# window-watchdog.net
KiCad netlist of a schematic drawn in Altium Designer
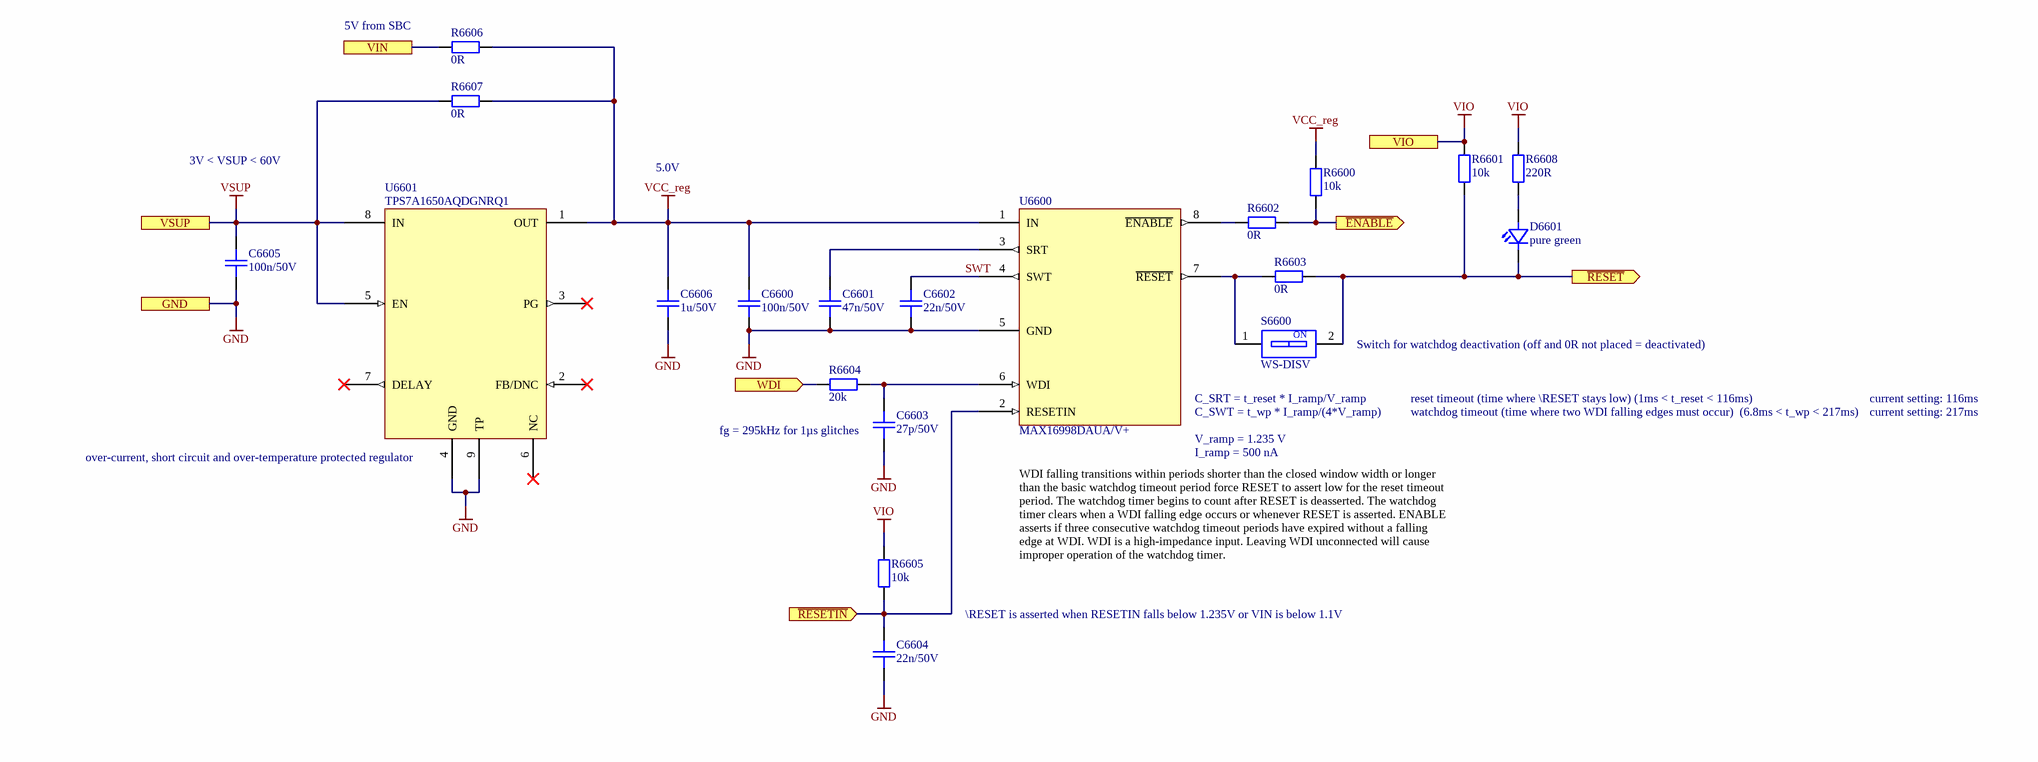
[diagram p0: window-watchdog.SchDoc]

(export (version "E")
  (design (tool "Eeschema 10.0.6"))
  (components
    (comp (ref "C6600")
      (value "100n/50V")
      (footprint "CAPC1005X06N")
      (description "MLCC")
      (fields (field (name "PART NUMBER") "gen_C_ceramic_100n_50V_X7R_0402"))
      (libsource (lib "OE750") (part "C"))
    )
    (comp (ref "C6601")
      (value "47n/50V")
      (footprint "CAPC1005X06N")
      (description "MLCC")
      (fields (field (name "PART NUMBER") "gen_C_ceramic_47n_50V_X7R_0402"))
      (libsource (lib "OE750") (part "C"))
    )
    (comp (ref "C6602")
      (value "22n/50V")
      (footprint "CAPC1005X06N")
      (description "MLCC")
      (fields (field (name "PART NUMBER") "gen_C_ceramic_22n_50V_X7R_0402"))
      (libsource (lib "OE750") (part "C"))
    )
    (comp (ref "C6603")
      (value "27p/50V")
      (footprint "CAPC1608X08N")
      (description "MLCC")
      (fields (field (name "PART NUMBER") "gen_C_ceramic_27p_50V_NP0_0603"))
      (libsource (lib "OE750") (part "C"))
    )
    (comp (ref "C6604")
      (value "22n/50V")
      (footprint "CAPC1005X06N")
      (description "MLCC")
      (fields (field (name "PART NUMBER") "gen_C_ceramic_22n_50V_X7R_0402"))
      (libsource (lib "OE750") (part "C"))
    )
    (comp (ref "C6605")
      (value "100n/50V")
      (footprint "CAPC1005X06N")
      (description "MLCC")
      (fields (field (name "PART NUMBER") "gen_C_ceramic_100n_50V_X7R_0402"))
      (libsource (lib "OE750") (part "C"))
    )
    (comp (ref "C6606")
      (value "1u/50V")
      (footprint "CAPC1608X08N")
      (description "MLCC")
      (fields (field (name "PART NUMBER") "gen_C_ceramic_1u_50V_X7R_0603") (field (name "TOLERANCE") "± 10%"))
      (libsource (lib "OE750") (part "C"))
    )
    (comp (ref "D6601")
      (value "pure green")
      (footprint "LEDC1608X07N")
      (description "TLMP1100-GS08")
      (fields (field (name "PART NUMBER") "LED_0603_pure_green_AECQ") (field (name "MANUFACTURER") "Vishay"))
      (libsource (lib "OE750") (part "D_LED"))
    )
    (comp (ref "R6600")
      (value "10k")
      (footprint "RESC1005X04N")
      (description "SMD Resistor 10k 0402")
      (fields (field (name "PART NUMBER") "gen_R_10k_0402") (field (name "TOLERANCE") "1%"))
      (libsource (lib "OE750") (part "R"))
    )
    (comp (ref "R6601")
      (value "10k")
      (footprint "RESC1005X04N")
      (description "SMD Resistor 10k 0402")
      (fields (field (name "PART NUMBER") "gen_R_10k_0402") (field (name "TOLERANCE") "1%"))
      (libsource (lib "OE750") (part "R"))
    )
    (comp (ref "R6602")
      (value "0R")
      (footprint "RESC1005X04N")
      (description "SMD Resistor 0R 0402")
      (fields (field (name "PART NUMBER") "gen_R_0R_0402") (field (name "POWER") "0.063W"))
      (libsource (lib "OE750") (part "R"))
    )
    (comp (ref "R6603")
      (value "0R")
      (footprint "RESC1005X04N")
      (description "SMD Resistor 0R 0402")
      (fields (field (name "PART NUMBER") "gen_R_0R_0402") (field (name "POWER") "0.063W"))
      (libsource (lib "OE750") (part "R"))
    )
    (comp (ref "R6604")
      (value "20k")
      (footprint "RESC1005X04N")
      (description "SMD Resistor 20k 0402")
      (fields (field (name "PART NUMBER") "gen_R_20k_0402") (field (name "TOLERANCE") "1%"))
      (libsource (lib "OE750") (part "R"))
    )
    (comp (ref "R6605")
      (value "10k")
      (footprint "RESC1005X04N")
      (description "SMD Resistor 10k 0402")
      (fields (field (name "PART NUMBER") "gen_R_10k_0402") (field (name "TOLERANCE") "1%"))
      (libsource (lib "OE750") (part "R"))
    )
    (comp (ref "R6606")
      (value "0R")
      (footprint "RESC1005X04N")
      (description "SMD Resistor 0R 0402")
      (fields (field (name "PART NUMBER") "gen_R_0R_0402") (field (name "POWER") "0.063W"))
      (libsource (lib "OE750") (part "R"))
    )
    (comp (ref "R6607")
      (value "0R")
      (footprint "RESC1005X04N")
      (description "SMD Resistor 0R 0402")
      (fields (field (name "PART NUMBER") "gen_R_0R_0402") (field (name "POWER") "0.063W"))
      (libsource (lib "OE750") (part "R"))
    )
    (comp (ref "R6608")
      (value "220R")
      (footprint "RESC1005X04N")
      (description "SMD Resistor 220R 0402")
      (fields (field (name "PART NUMBER") "gen_R_220R_0402") (field (name "TOLERANCE") "1%"))
      (libsource (lib "OE750") (part "R"))
    )
    (comp (ref "S6600")
      (value "WS-DISV")
      (footprint "WE_416131160801")
      (description "WS-DISV Small Compact SMT DipSwitch")
      (fields (field (name "PART NUMBER") "WE_416131160801") (field (name "MANUFACTURER") "Würth Elektronik"))
      (libsource (lib "OE750") (part "WE_416131160801"))
    )
    (comp (ref "U6600")
      (value "MAX16998DAUA/V+")
      (footprint "MAX16998-uSOP8")
      (description "High-Voltage Watchdog Timers with Adjustable Timeout Delay")
      (fields (field (name "MANUFACTURER") "Maxim Integrated"))
      (libsource (lib "OE750") (part "MAX16998"))
    )
    (comp (ref "U6601")
      (value "TPS7A1650AQDGNRQ1")
      (footprint "TPS7A16A-Q1")
      (description "Automotive 60-V, 5-µA IQ, 100-mA low-dropout (LDO) voltage regulator with enable and power good")
      (fields (field (name "MANUFACTURER") "Texas Instruments"))
      (libsource (lib "OE750") (part "TPS7A16A"))
    )
  )
  (nets
    (net (code "1") (name "/ENABLE") (class "Default")
      (node (ref "R6600") (pin "1") (pinfunction "1_1") (pintype "passive"))
      (node (ref "R6602") (pin "2") (pinfunction "2_2") (pintype "passive"))
    )
    (net (code "2") (name "/RESET") (class "Default")
      (node (ref "D6601") (pin "1") (pinfunction "C_1") (pintype "passive"))
      (node (ref "R6601") (pin "1") (pinfunction "1_1") (pintype "passive"))
      (node (ref "R6603") (pin "2") (pinfunction "2_2") (pintype "passive"))
      (node (ref "S6600") (pin "2") (pinfunction "2_2") (pintype "passive"))
    )
    (net (code "3") (name "/RESETIN") (class "Default")
      (node (ref "C6604") (pin "2") (pinfunction "2_2") (pintype "passive"))
      (node (ref "R6605") (pin "1") (pinfunction "1_1") (pintype "passive"))
      (node (ref "U6600") (pin "2") (pinfunction "RESETIN_2") (pintype "input"))
    )
    (net (code "4") (name "/SWT") (class "Default")
      (node (ref "C6602") (pin "2") (pinfunction "2_2") (pintype "passive"))
      (node (ref "U6600") (pin "4") (pinfunction "SWT_4") (pintype "output"))
    )
    (net (code "5") (name "/VIN") (class "Default")
      (node (ref "R6606") (pin "1") (pinfunction "1_1") (pintype "passive"))
    )
    (net (code "6") (name "/WDI") (class "Default")
      (node (ref "R6604") (pin "1") (pinfunction "1_1") (pintype "passive"))
    )
    (net (code "7") (name "GND") (class "Default")
      (node (ref "C6600") (pin "1") (pinfunction "1_1") (pintype "passive"))
      (node (ref "C6601") (pin "1") (pinfunction "1_1") (pintype "passive"))
      (node (ref "C6602") (pin "1") (pinfunction "1_1") (pintype "passive"))
      (node (ref "C6603") (pin "1") (pinfunction "1_1") (pintype "passive"))
      (node (ref "C6604") (pin "1") (pinfunction "1_1") (pintype "passive"))
      (node (ref "C6605") (pin "1") (pinfunction "1_1") (pintype "passive"))
      (node (ref "C6606") (pin "1") (pinfunction "1_1") (pintype "passive"))
      (node (ref "U6600") (pin "5") (pinfunction "GND_5") (pintype "power_in"))
      (node (ref "U6601") (pin "4") (pinfunction "GND_4") (pintype "power_in"))
      (node (ref "U6601") (pin "9") (pinfunction "TP_9") (pintype "power_in"))
    )
    (net (code "8") (name "Net-(D6601-A)") (class "Default")
      (node (ref "D6601") (pin "2") (pinfunction "A_2") (pintype "passive"))
      (node (ref "R6608") (pin "1") (pinfunction "1_1") (pintype "passive"))
    )
    (net (code "9") (name "Net-(U6600-ENABLE)") (class "Default")
      (node (ref "R6602") (pin "1") (pinfunction "1_1") (pintype "passive"))
      (node (ref "U6600") (pin "8") (pinfunction "ENABLE_8") (pintype "output"))
    )
    (net (code "10") (name "Net-(U6600-RESET)") (class "Default")
      (node (ref "R6603") (pin "1") (pinfunction "1_1") (pintype "passive"))
      (node (ref "S6600") (pin "1") (pinfunction "1_1") (pintype "passive"))
      (node (ref "U6600") (pin "7") (pinfunction "RESET_7") (pintype "output"))
    )
    (net (code "11") (name "Net-(U6600-SRT)") (class "Default")
      (node (ref "C6601") (pin "2") (pinfunction "2_2") (pintype "passive"))
      (node (ref "U6600") (pin "3") (pinfunction "SRT_3") (pintype "output"))
    )
    (net (code "12") (name "Net-(U6600-WDI)") (class "Default")
      (node (ref "C6603") (pin "2") (pinfunction "2_2") (pintype "passive"))
      (node (ref "R6604") (pin "2") (pinfunction "2_2") (pintype "passive"))
      (node (ref "U6600") (pin "6") (pinfunction "WDI_6") (pintype "input"))
    )
    (net (code "13") (name "VCC_reg") (class "Default")
      (node (ref "C6600") (pin "2") (pinfunction "2_2") (pintype "passive"))
      (node (ref "C6606") (pin "2") (pinfunction "2_2") (pintype "passive"))
      (node (ref "R6600") (pin "2") (pinfunction "2_2") (pintype "passive"))
      (node (ref "R6606") (pin "2") (pinfunction "2_2") (pintype "passive"))
      (node (ref "R6607") (pin "2") (pinfunction "2_2") (pintype "passive"))
      (node (ref "U6600") (pin "1") (pinfunction "IN_1") (pintype "power_in"))
      (node (ref "U6601") (pin "1") (pinfunction "OUT_1") (pintype "power_in"))
    )
    (net (code "14") (name "VIO") (class "Default")
      (node (ref "R6601") (pin "2") (pinfunction "2_2") (pintype "passive"))
      (node (ref "R6605") (pin "2") (pinfunction "2_2") (pintype "passive"))
      (node (ref "R6608") (pin "2") (pinfunction "2_2") (pintype "passive"))
    )
    (net (code "15") (name "VSUP") (class "Default")
      (node (ref "C6605") (pin "2") (pinfunction "2_2") (pintype "passive"))
      (node (ref "R6607") (pin "1") (pinfunction "1_1") (pintype "passive"))
      (node (ref "U6601") (pin "5") (pinfunction "EN_5") (pintype "input"))
      (node (ref "U6601") (pin "8") (pinfunction "IN_8") (pintype "power_in"))
    )
    (net (code "16") (name "unconnected-(U6601-DELAY-Pad7)") (class "Default")
      (node (ref "U6601") (pin "7") (pinfunction "DELAY_7") (pintype "output+no_connect"))
    )
    (net (code "17") (name "unconnected-(U6601-FB{slash}DNC-Pad2)") (class "Default")
      (node (ref "U6601") (pin "2") (pinfunction "FB/DNC_2") (pintype "input+no_connect"))
    )
    (net (code "18") (name "unconnected-(U6601-NC-Pad6)") (class "Default")
      (node (ref "U6601") (pin "6") (pinfunction "NC_6") (pintype "passive+no_connect"))
    )
    (net (code "19") (name "unconnected-(U6601-PG-Pad3)") (class "Default")
      (node (ref "U6601") (pin "3") (pinfunction "PG_3") (pintype "output+no_connect"))
    )
  )
)
